# WaterAlarmESP12-5.net
KiCad netlist of a schematic drawn in EAGLE
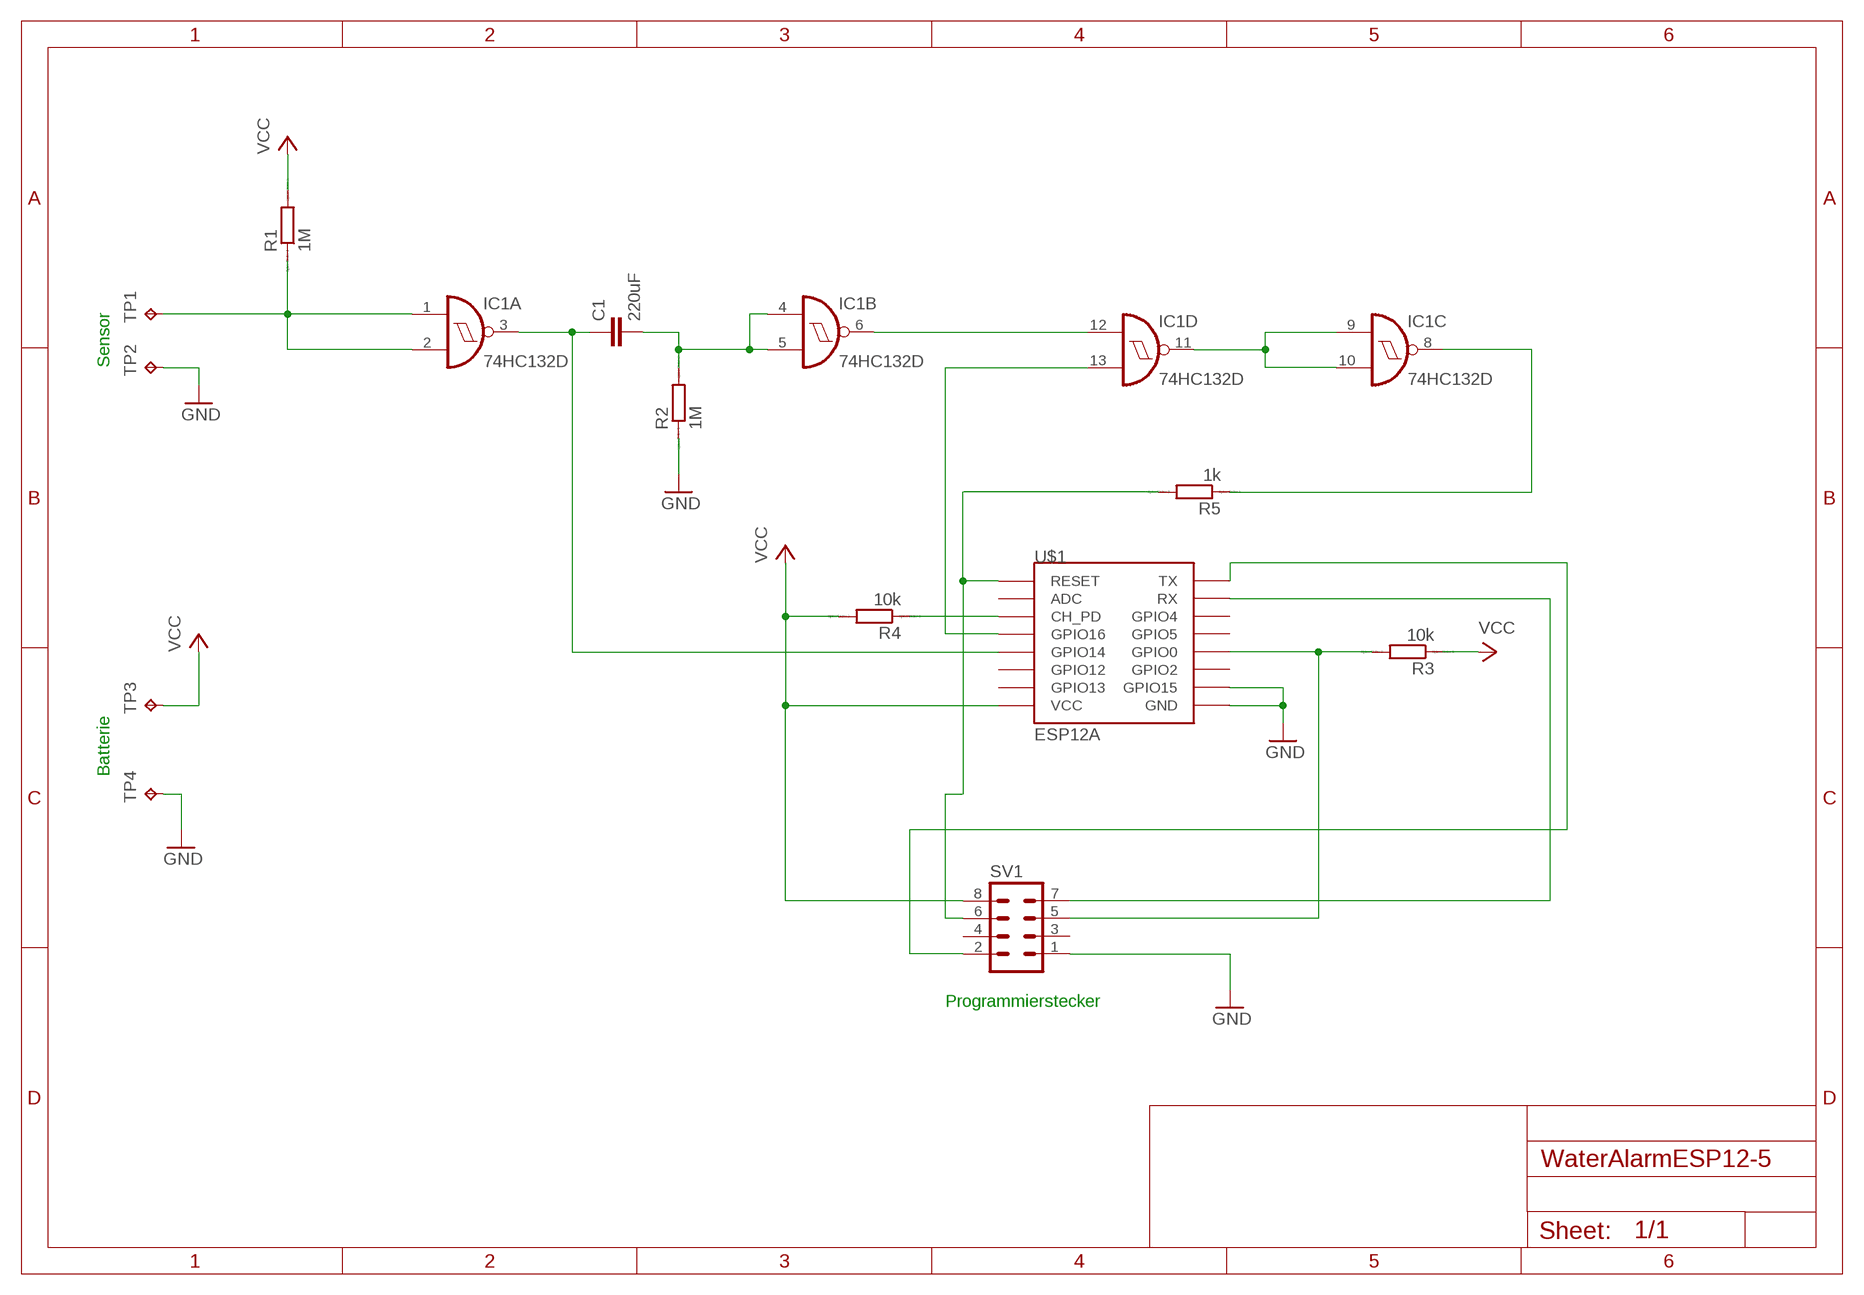
[diagram p0: schematic, sheet 1]

(export (version "E")
  (design (tool "Eeschema 10.0.6"))
  (components
    (comp (ref "C1")
      (value "220uF")
      (footprint "eagle-import:C1206")
      (libsource (lib "eagle-import") (part "C-EUC1206"))
    )
    (comp (ref "IC1")
      (value "74HC132D")
      (footprint "eagle-import:SO14")
      (libsource (lib "eagle-import") (part "74132DHC"))
    )
    (comp (ref "R1")
      (value "1M")
      (footprint "eagle-import:R1206")
      (libsource (lib "eagle-import") (part "RR1206"))
    )
    (comp (ref "R2")
      (value "1M")
      (footprint "eagle-import:R1206")
      (libsource (lib "eagle-import") (part "RR1206"))
    )
    (comp (ref "R3")
      (value "10k")
      (footprint "eagle-import:R1206")
      (libsource (lib "eagle-import") (part "RR1206"))
    )
    (comp (ref "R4")
      (value "10k")
      (footprint "eagle-import:R1206")
      (libsource (lib "eagle-import") (part "RR1206"))
    )
    (comp (ref "R5")
      (value "1k")
      (footprint "eagle-import:R1206")
      (libsource (lib "eagle-import") (part "RR1206"))
    )
    (comp (ref "SV1")
      (value "MA04-2")
      (footprint "eagle-import:MA04-2")
      (libsource (lib "eagle-import") (part "MA04-2"))
    )
    (comp (ref "TP1")
      (value "TPPAD1-17")
      (footprint "eagle-import:P1-17")
      (libsource (lib "eagle-import") (part "TPPAD1-17"))
    )
    (comp (ref "TP2")
      (value "TPPAD1-17")
      (footprint "eagle-import:P1-17")
      (libsource (lib "eagle-import") (part "TPPAD1-17"))
    )
    (comp (ref "TP3")
      (value "TPPAD1-17")
      (footprint "eagle-import:P1-17")
      (libsource (lib "eagle-import") (part "TPPAD1-17"))
    )
    (comp (ref "TP4")
      (value "TPPAD1-17")
      (footprint "eagle-import:P1-17")
      (libsource (lib "eagle-import") (part "TPPAD1-17"))
    )
    (comp (ref "U$1")
      (value "ESP12A")
      (footprint "eagle-import:ESP12A")
      (libsource (lib "eagle-import") (part "ESP12A"))
    )
  )
  (nets
    (net (code "1") (name "GND") (class "Default")
      (node (ref "R2") (pin "1") (pinfunction "1_1") (pintype "passive"))
      (node (ref "SV1") (pin "1") (pinfunction "1_1") (pintype "passive"))
      (node (ref "TP2") (pin "TP") (pinfunction "TP_TP") (pintype "input"))
      (node (ref "TP4") (pin "TP") (pinfunction "TP_TP") (pintype "input"))
      (node (ref "U$1") (pin "GND") (pinfunction "GND_GND") (pintype "bidirectional"))
      (node (ref "U$1") (pin "GPIO15") (pinfunction "GPIO15_GPIO15") (pintype "bidirectional"))
    )
    (net (code "2") (name "Net-(IC1A-I0)") (class "Default")
      (node (ref "IC1") (pin "1") (pinfunction "I0_1") (pintype "input"))
      (node (ref "IC1") (pin "2") (pinfunction "I1_2") (pintype "input"))
      (node (ref "R1") (pin "1") (pinfunction "1_1") (pintype "passive"))
      (node (ref "TP1") (pin "TP") (pinfunction "TP_TP") (pintype "input"))
    )
    (net (code "3") (name "Net-(IC1A-O)") (class "Default")
      (node (ref "C1") (pin "1") (pinfunction "1_1") (pintype "passive"))
      (node (ref "IC1") (pin "3") (pinfunction "O_3") (pintype "output"))
      (node (ref "U$1") (pin "GPIO14") (pinfunction "GPIO14_GPIO14") (pintype "bidirectional"))
    )
    (net (code "4") (name "Net-(IC1B-I0)") (class "Default")
      (node (ref "C1") (pin "2") (pinfunction "2_2") (pintype "passive"))
      (node (ref "IC1") (pin "4") (pinfunction "I0_4") (pintype "input"))
      (node (ref "IC1") (pin "5") (pinfunction "I1_5") (pintype "input"))
      (node (ref "R2") (pin "2") (pinfunction "2_2") (pintype "passive"))
    )
    (net (code "5") (name "Net-(IC1B-O)") (class "Default")
      (node (ref "IC1") (pin "12") (pinfunction "I0_12") (pintype "input"))
      (node (ref "IC1") (pin "6") (pinfunction "O_6") (pintype "output"))
    )
    (net (code "6") (name "Net-(IC1C-I0)") (class "Default")
      (node (ref "IC1") (pin "10") (pinfunction "I1_10") (pintype "input"))
      (node (ref "IC1") (pin "11") (pinfunction "O_11") (pintype "output"))
      (node (ref "IC1") (pin "9") (pinfunction "I0_9") (pintype "input"))
    )
    (net (code "7") (name "Net-(IC1C-O)") (class "Default")
      (node (ref "IC1") (pin "8") (pinfunction "O_8") (pintype "output"))
      (node (ref "R5") (pin "1") (pinfunction "1_1") (pintype "passive"))
    )
    (net (code "8") (name "Net-(IC1D-I1)") (class "Default")
      (node (ref "IC1") (pin "13") (pinfunction "I1_13") (pintype "input"))
      (node (ref "U$1") (pin "GPIO16") (pinfunction "GPIO16_GPIO16") (pintype "bidirectional"))
    )
    (net (code "9") (name "Net-(R3-Pad2)") (class "Default")
      (node (ref "R3") (pin "2") (pinfunction "2_2") (pintype "passive"))
      (node (ref "SV1") (pin "5") (pinfunction "5_5") (pintype "passive"))
      (node (ref "U$1") (pin "GPIO0") (pinfunction "GPIO0_GPIO0") (pintype "bidirectional"))
    )
    (net (code "10") (name "Net-(R4-Pad1)") (class "Default")
      (node (ref "R4") (pin "1") (pinfunction "1_1") (pintype "passive"))
      (node (ref "U$1") (pin "CH_PD") (pinfunction "CH_PD_CH_PD") (pintype "bidirectional"))
    )
    (net (code "11") (name "Net-(R5-Pad2)") (class "Default")
      (node (ref "R5") (pin "2") (pinfunction "2_2") (pintype "passive"))
      (node (ref "SV1") (pin "6") (pinfunction "6_6") (pintype "passive"))
      (node (ref "U$1") (pin "RESET") (pinfunction "RESET_RESET") (pintype "bidirectional"))
    )
    (net (code "12") (name "Net-(SV1-Pad2)") (class "Default")
      (node (ref "SV1") (pin "2") (pinfunction "2_2") (pintype "passive"))
      (node (ref "U$1") (pin "TX") (pinfunction "TX_TX") (pintype "bidirectional"))
    )
    (net (code "13") (name "Net-(SV1-Pad7)") (class "Default")
      (node (ref "SV1") (pin "7") (pinfunction "7_7") (pintype "passive"))
      (node (ref "U$1") (pin "RX") (pinfunction "RX_RX") (pintype "bidirectional"))
    )
    (net (code "14") (name "VCC") (class "Default")
      (node (ref "R1") (pin "2") (pinfunction "2_2") (pintype "passive"))
      (node (ref "R3") (pin "1") (pinfunction "1_1") (pintype "passive"))
      (node (ref "R4") (pin "2") (pinfunction "2_2") (pintype "passive"))
      (node (ref "SV1") (pin "8") (pinfunction "8_8") (pintype "passive"))
      (node (ref "TP3") (pin "TP") (pinfunction "TP_TP") (pintype "input"))
      (node (ref "U$1") (pin "VCC") (pinfunction "VCC_VCC") (pintype "bidirectional"))
    )
    (net (code "15") (name "unconnected-(SV1-Pad3)") (class "Default")
      (node (ref "SV1") (pin "3") (pinfunction "3_3") (pintype "passive"))
    )
    (net (code "16") (name "unconnected-(SV1-Pad4)") (class "Default")
      (node (ref "SV1") (pin "4") (pinfunction "4_4") (pintype "passive"))
    )
    (net (code "17") (name "unconnected-(U$1-PadADC)") (class "Default")
      (node (ref "U$1") (pin "ADC") (pinfunction "ADC_ADC") (pintype "bidirectional"))
    )
    (net (code "18") (name "unconnected-(U$1-PadGPIO2)") (class "Default")
      (node (ref "U$1") (pin "GPIO2") (pinfunction "GPIO2_GPIO2") (pintype "bidirectional"))
    )
    (net (code "19") (name "unconnected-(U$1-PadGPIO4)") (class "Default")
      (node (ref "U$1") (pin "GPIO4") (pinfunction "GPIO4_GPIO4") (pintype "bidirectional"))
    )
    (net (code "20") (name "unconnected-(U$1-PadGPIO5)") (class "Default")
      (node (ref "U$1") (pin "GPIO5") (pinfunction "GPIO5_GPIO5") (pintype "bidirectional"))
    )
    (net (code "21") (name "unconnected-(U$1-PadGPIO12)") (class "Default")
      (node (ref "U$1") (pin "GPIO12") (pinfunction "GPIO12_GPIO12") (pintype "bidirectional"))
    )
    (net (code "22") (name "unconnected-(U$1-PadGPIO13)") (class "Default")
      (node (ref "U$1") (pin "GPIO13") (pinfunction "GPIO13_GPIO13") (pintype "bidirectional"))
    )
  )
)
